# breadboard-lipo-switch.net
KiCad netlist of a schematic drawn in EAGLE
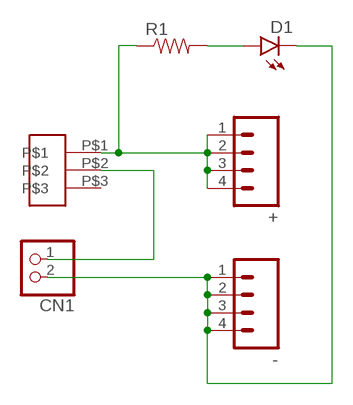
[diagram p0: schematic, sheet 1]

(export (version "E")
  (design (tool "Eeschema 10.0.6"))
  (components
    (comp (ref "+")
      (value "M04PTH")
      (footprint "eagle-import:1X04")
      (libsource (lib "eagle-import") (part "M04PTH"))
    )
    (comp (ref "-")
      (value "M04PTH")
      (footprint "eagle-import:1X04")
      (libsource (lib "eagle-import") (part "M04PTH"))
    )
    (comp (ref "CN1")
      (value "JST_2PIN-SMT-RA")
      (footprint "eagle-import:JST-PH-2-SMT-RA")
      (libsource (lib "eagle-import") (part "JST_2PIN-SMT-RA"))
    )
    (comp (ref "D1")
      (value "LED0603")
      (footprint "eagle-import:LED-0603")
      (libsource (lib "eagle-import") (part "LED0603"))
    )
    (comp (ref "R1")
      (value "RESISTOR0603-RES")
      (footprint "eagle-import:0603-RES")
      (libsource (lib "eagle-import") (part "RESISTOR0603-RES"))
    )
    (comp (ref "U$1")
      (value "OS102-SPDT-SWITCH")
      (footprint "eagle-import:OS102-SPDT-SWITCH")
      (libsource (lib "eagle-import") (part "OS102-SPDT-SWITCH"))
    )
  )
  (nets
    (net (code "1") (name "Net-(+-Pad1)") (class "Default")
      (node (ref "+") (pin "1") (pinfunction "1_1") (pintype "passive"))
      (node (ref "+") (pin "2") (pinfunction "2_2") (pintype "passive"))
      (node (ref "+") (pin "3") (pinfunction "3_3") (pintype "passive"))
      (node (ref "+") (pin "4") (pinfunction "4_4") (pintype "passive"))
      (node (ref "R1") (pin "1") (pinfunction "1_1") (pintype "passive"))
      (node (ref "U$1") (pin "P$1") (pinfunction "P$1_P$1") (pintype "bidirectional"))
    )
    (net (code "2") (name "Net-(CN1-1)") (class "Default")
      (node (ref "-") (pin "1") (pinfunction "1_1") (pintype "passive"))
      (node (ref "-") (pin "2") (pinfunction "2_2") (pintype "passive"))
      (node (ref "-") (pin "3") (pinfunction "3_3") (pintype "passive"))
      (node (ref "-") (pin "4") (pinfunction "4_4") (pintype "passive"))
      (node (ref "CN1") (pin "2") (pinfunction "1_2") (pintype "passive"))
      (node (ref "D1") (pin "C") (pinfunction "C_C") (pintype "passive"))
    )
    (net (code "3") (name "Net-(CN1-2)") (class "Default")
      (node (ref "CN1") (pin "1") (pinfunction "2_1") (pintype "passive"))
      (node (ref "U$1") (pin "P$2") (pinfunction "P$2_P$2") (pintype "bidirectional"))
    )
    (net (code "4") (name "Net-(D1-PadA)") (class "Default")
      (node (ref "D1") (pin "A") (pinfunction "A_A") (pintype "passive"))
      (node (ref "R1") (pin "2") (pinfunction "2_2") (pintype "passive"))
    )
    (net (code "5") (name "unconnected-(U$1-PadP$3)") (class "Default")
      (node (ref "U$1") (pin "P$3") (pinfunction "P$3_P$3") (pintype "bidirectional"))
    )
  )
)
